# OledBoardSchematicV1.net
KiCad netlist of a schematic drawn in EAGLE
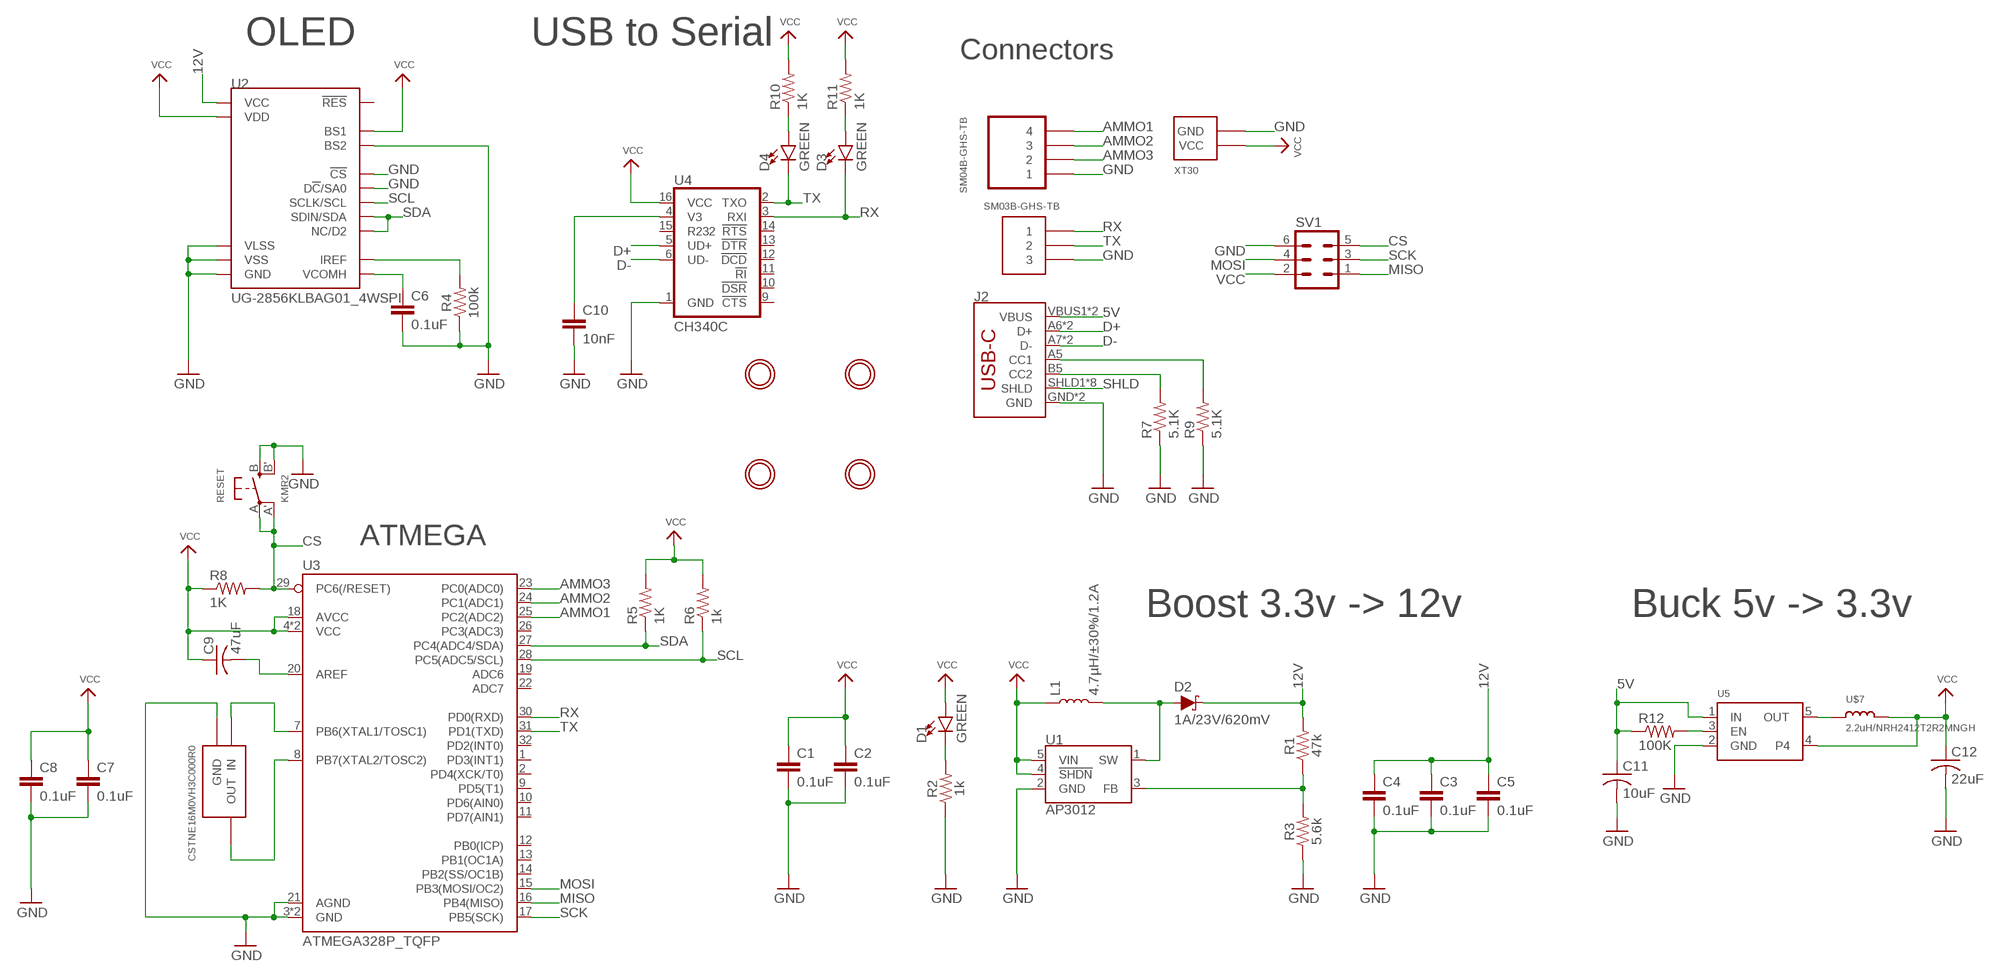
[diagram p0: schematic, sheet 1]

(export (version "E")
  (design (tool "Eeschema 10.0.6"))
  (components
    (comp (ref "C1")
      (value "0.1uF")
      (footprint "eagle-import:0603")
      (libsource (lib "eagle-import") (part "0.1UF-0603-25V-(+80/-20%)"))
    )
    (comp (ref "C2")
      (value "0.1uF")
      (footprint "eagle-import:0603")
      (libsource (lib "eagle-import") (part "0.1UF-0603-25V-(+80/-20%)"))
    )
    (comp (ref "C3")
      (value "0.1uF")
      (footprint "eagle-import:0603")
      (libsource (lib "eagle-import") (part "0.1UF-0603-25V-(+80/-20%)"))
    )
    (comp (ref "C4")
      (value "0.1uF")
      (footprint "eagle-import:0603")
      (libsource (lib "eagle-import") (part "0.1UF-0603-25V-(+80/-20%)"))
    )
    (comp (ref "C5")
      (value "0.1uF")
      (footprint "eagle-import:0603")
      (libsource (lib "eagle-import") (part "0.1UF-0603-25V-(+80/-20%)"))
    )
    (comp (ref "C6")
      (value "0.1uF")
      (footprint "eagle-import:0603")
      (libsource (lib "eagle-import") (part "0.1UF-0603-25V-(+80/-20%)"))
    )
    (comp (ref "C7")
      (value "0.1uF")
      (footprint "eagle-import:0603")
      (libsource (lib "eagle-import") (part "0.1UF-0603-25V-(+80/-20%)"))
    )
    (comp (ref "C8")
      (value "0.1uF")
      (footprint "eagle-import:0603")
      (libsource (lib "eagle-import") (part "0.1UF-0603-25V-(+80/-20%)"))
    )
    (comp (ref "C9")
      (value "47uF")
      (footprint "eagle-import:C0603")
      (libsource (lib "eagle-import") (part "C-USC0603"))
    )
    (comp (ref "C10")
      (value "10nF")
      (footprint "eagle-import:0603")
      (libsource (lib "eagle-import") (part "0.1UF-0603-25V-(+80/-20%)"))
    )
    (comp (ref "C11")
      (value "10uF")
      (footprint "eagle-import:C0603")
      (libsource (lib "eagle-import") (part "C-USC0603"))
    )
    (comp (ref "C12")
      (value "22uF")
      (footprint "eagle-import:C0603")
      (libsource (lib "eagle-import") (part "C-USC0603"))
    )
    (comp (ref "D1")
      (value "GREEN")
      (footprint "eagle-import:LED-0603")
      (libsource (lib "eagle-import") (part "LED0603"))
    )
    (comp (ref "D2")
      (value "1A/23V/620mV")
      (footprint "eagle-import:SOD-323")
      (libsource (lib "eagle-import") (part "DIODE-SCHOTTKY-BAT20J"))
    )
    (comp (ref "D3")
      (value "GREEN")
      (footprint "eagle-import:LED-0603")
      (libsource (lib "eagle-import") (part "LED-GREEN0603"))
    )
    (comp (ref "D4")
      (value "GREEN")
      (footprint "eagle-import:LED-0603")
      (libsource (lib "eagle-import") (part "LED-GREEN0603"))
    )
    (comp (ref "J2")
      (value "USB_C2-LAYER")
      (footprint "eagle-import:USB-C-16P")
      (libsource (lib "eagle-import") (part "USB_C2-LAYER"))
    )
    (comp (ref "L1")
      (value "4.7µH/±30%/1.2A")
      (footprint "eagle-import:INDUCTOR_4.7UH")
      (libsource (lib "eagle-import") (part "INDUCTOR-CDRH-4.7UH"))
    )
    (comp (ref "R1")
      (value "47k")
      (footprint "eagle-import:0603")
      (libsource (lib "eagle-import") (part "47KOHM-0603-1/10W-1%"))
    )
    (comp (ref "R2")
      (value "1k")
      (footprint "eagle-import:0603")
      (libsource (lib "eagle-import") (part "1KOHM-0603-1/10W-1%"))
    )
    (comp (ref "R3")
      (value "5.6k")
      (footprint "eagle-import:0603")
      (libsource (lib "eagle-import") (part "5.6KOHM-0603-1/10W-1%"))
    )
    (comp (ref "R4")
      (value "100k")
      (footprint "eagle-import:0603")
      (libsource (lib "eagle-import") (part "100KOHM-0603-1/10W-1%"))
    )
    (comp (ref "R5")
      (value "1K")
      (footprint "eagle-import:R0603")
      (libsource (lib "eagle-import") (part "R-US_R0603"))
    )
    (comp (ref "R6")
      (value "1k")
      (footprint "eagle-import:R0603")
      (libsource (lib "eagle-import") (part "R-US_R0603"))
    )
    (comp (ref "R7")
      (value "5.1K")
      (footprint "eagle-import:R0603")
      (libsource (lib "eagle-import") (part "R-US_R0603"))
    )
    (comp (ref "R8")
      (value "1K")
      (footprint "eagle-import:R0603")
      (libsource (lib "eagle-import") (part "R-US_R0603"))
    )
    (comp (ref "R9")
      (value "5.1K")
      (footprint "eagle-import:R0603")
      (libsource (lib "eagle-import") (part "R-US_R0603"))
    )
    (comp (ref "R10")
      (value "1K")
      (footprint "eagle-import:R0603")
      (libsource (lib "eagle-import") (part "R-US_R0603"))
    )
    (comp (ref "R11")
      (value "1K")
      (footprint "eagle-import:R0603")
      (libsource (lib "eagle-import") (part "R-US_R0603"))
    )
    (comp (ref "R12")
      (value "100K")
      (footprint "eagle-import:R0603")
      (libsource (lib "eagle-import") (part "R-US_R0603"))
    )
    (comp (ref "RESET")
      (value "KMR2")
      (footprint "eagle-import:BTN_KMR2_4.6X2.8")
      (libsource (lib "eagle-import") (part "SWITCH_TACT_SMT4.6X2.8"))
    )
    (comp (ref "SV1")
      (value "MA03-2")
      (footprint "eagle-import:MA03-2")
      (libsource (lib "eagle-import") (part "MA03-2"))
    )
    (comp (ref "U$1")
      (value "MOUNTINGHOLE2.5")
      (footprint "eagle-import:MOUNTINGHOLE_2.5_PLATED")
      (libsource (lib "eagle-import") (part "MOUNTINGHOLE2.5"))
    )
    (comp (ref "U$2")
      (value "MOUNTINGHOLE2.5")
      (footprint "eagle-import:MOUNTINGHOLE_2.5_PLATED")
      (libsource (lib "eagle-import") (part "MOUNTINGHOLE2.5"))
    )
    (comp (ref "U$3")
      (value "MOUNTINGHOLE2.5")
      (footprint "eagle-import:MOUNTINGHOLE_2.5_PLATED")
      (libsource (lib "eagle-import") (part "MOUNTINGHOLE2.5"))
    )
    (comp (ref "U$4")
      (value "MOUNTINGHOLE2.5")
      (footprint "eagle-import:MOUNTINGHOLE_2.5_PLATED")
      (libsource (lib "eagle-import") (part "MOUNTINGHOLE2.5"))
    )
    (comp (ref "U$5")
      (value "SM04B-GHS-TB")
      (footprint "eagle-import:SM04B-GHS-TB")
      (libsource (lib "eagle-import") (part "SM04B-GHS-TB"))
    )
    (comp (ref "U$6")
      (value "CSTNE16M0VH3C000R0")
      (footprint "eagle-import:CSTNE16M0VH3C000R0")
      (libsource (lib "eagle-import") (part "CSTNE16M0VH3C000R0"))
    )
    (comp (ref "U$7")
      (value "2.2uH/NRH2412T2R2MNGH")
      (footprint "eagle-import:MDKK1616T2R2MM")
      (libsource (lib "eagle-import") (part "MDKK1616T2R2MM"))
    )
    (comp (ref "U$8")
      (value "SM03B-GHS-TB")
      (footprint "eagle-import:SM03B-GHS-TB")
      (libsource (lib "eagle-import") (part "SM03B-GHS-TB"))
    )
    (comp (ref "U$9")
      (value "XT30PW-M")
      (footprint "eagle-import:XT30")
      (libsource (lib "eagle-import") (part "XT30PW-M"))
    )
    (comp (ref "U1")
      (value "AP3012")
      (footprint "eagle-import:SOT23-5")
      (libsource (lib "eagle-import") (part "AP3012"))
    )
    (comp (ref "U2")
      (value "UG-2856KLBAG01_4WSPI")
      (footprint "eagle-import:FPC05024-42201")
      (libsource (lib "eagle-import") (part "UG-2856KLBAG01_4WSPI"))
    )
    (comp (ref "U3")
      (value "ATMEGA328P_TQFP")
      (footprint "eagle-import:TQFP32-08")
      (libsource (lib "eagle-import") (part "ATMEGA328P_TQFP"))
    )
    (comp (ref "U4")
      (value "CH340C")
      (footprint "eagle-import:SO016")
      (libsource (lib "eagle-import") (part "CH340C"))
    )
    (comp (ref "U5")
      (value "VREG_SOT23-5")
      (footprint "eagle-import:SOT23-5")
      (libsource (lib "eagle-import") (part "VREG_SOT23-5"))
    )
  )
  (nets
    (net (code "1") (name "/5V") (class "Default")
      (node (ref "C11") (pin "1") (pinfunction "1_1") (pintype "passive"))
      (node (ref "J2") (pin "VBUS1") (pinfunction "VBUS_VBUS1") (pintype "bidirectional"))
      (node (ref "J2") (pin "VBUS2") (pinfunction "VBUS_VBUS2") (pintype "bidirectional"))
      (node (ref "R12") (pin "1") (pinfunction "1_1") (pintype "passive"))
      (node (ref "U5") (pin "1") (pinfunction "IN_1") (pintype "bidirectional"))
    )
    (net (code "2") (name "/12V") (class "Default")
      (node (ref "C3") (pin "1") (pinfunction "1_1") (pintype "passive"))
      (node (ref "C4") (pin "1") (pinfunction "1_1") (pintype "passive"))
      (node (ref "C5") (pin "1") (pinfunction "1_1") (pintype "passive"))
      (node (ref "D2") (pin "C") (pinfunction "C_C") (pintype "passive"))
      (node (ref "R1") (pin "2") (pinfunction "2_2") (pintype "passive"))
      (node (ref "U2") (pin "P$23") (pinfunction "VCC_P$23") (pintype "bidirectional"))
    )
    (net (code "3") (name "/AMMO1") (class "Default")
      (node (ref "U$5") (pin "4") (pinfunction "4_4") (pintype "bidirectional"))
      (node (ref "U3") (pin "25") (pinfunction "PC2(ADC2)_25") (pintype "bidirectional"))
    )
    (net (code "4") (name "/AMMO2") (class "Default")
      (node (ref "U$5") (pin "3") (pinfunction "3_3") (pintype "bidirectional"))
      (node (ref "U3") (pin "24") (pinfunction "PC1(ADC1)_24") (pintype "bidirectional"))
    )
    (net (code "5") (name "/AMMO3") (class "Default")
      (node (ref "U$5") (pin "2") (pinfunction "2_2") (pintype "bidirectional"))
      (node (ref "U3") (pin "23") (pinfunction "PC0(ADC0)_23") (pintype "bidirectional"))
    )
    (net (code "6") (name "/CS") (class "Default")
      (node (ref "R8") (pin "2") (pinfunction "2_2") (pintype "passive"))
      (node (ref "RESET") (pin "A") (pinfunction "P_A") (pintype "passive"))
      (node (ref "RESET") (pin "A'") (pinfunction "P1_A'") (pintype "passive"))
      (node (ref "SV1") (pin "5") (pinfunction "5_5") (pintype "passive"))
      (node (ref "U3") (pin "29") (pinfunction "PC6(/RESET)_29") (pintype "bidirectional"))
    )
    (net (code "7") (name "/D+") (class "Default")
      (node (ref "J2") (pin "A6") (pinfunction "D+_A6") (pintype "bidirectional"))
      (node (ref "J2") (pin "B6") (pinfunction "D+_B6") (pintype "bidirectional"))
      (node (ref "U4") (pin "5") (pinfunction "UD+_5") (pintype "bidirectional"))
    )
    (net (code "8") (name "/D-") (class "Default")
      (node (ref "J2") (pin "A7") (pinfunction "D-_A7") (pintype "bidirectional"))
      (node (ref "J2") (pin "B7") (pinfunction "D-_B7") (pintype "bidirectional"))
      (node (ref "U4") (pin "6") (pinfunction "UD-_6") (pintype "bidirectional"))
    )
    (net (code "9") (name "/MISO") (class "Default")
      (node (ref "SV1") (pin "1") (pinfunction "1_1") (pintype "passive"))
      (node (ref "U3") (pin "16") (pinfunction "PB4(MISO)_16") (pintype "bidirectional"))
    )
    (net (code "10") (name "/MOSI") (class "Default")
      (node (ref "SV1") (pin "4") (pinfunction "4_4") (pintype "passive"))
      (node (ref "U3") (pin "15") (pinfunction "PB3(MOSI/OC2)_15") (pintype "bidirectional"))
    )
    (net (code "11") (name "/RX") (class "Default")
      (node (ref "D3") (pin "C") (pinfunction "C_C") (pintype "passive"))
      (node (ref "U$8") (pin "P$3") (pinfunction "1_P$3") (pintype "bidirectional"))
      (node (ref "U3") (pin "30") (pinfunction "PD0(RXD)_30") (pintype "bidirectional"))
      (node (ref "U4") (pin "3") (pinfunction "RXI_3") (pintype "bidirectional"))
    )
    (net (code "12") (name "/SCK") (class "Default")
      (node (ref "SV1") (pin "3") (pinfunction "3_3") (pintype "passive"))
      (node (ref "U3") (pin "17") (pinfunction "PB5(SCK)_17") (pintype "bidirectional"))
    )
    (net (code "13") (name "/SCL") (class "Default")
      (node (ref "R6") (pin "1") (pinfunction "1_1") (pintype "passive"))
      (node (ref "U2") (pin "P$13") (pinfunction "SCLK/SCL_P$13") (pintype "bidirectional"))
      (node (ref "U3") (pin "28") (pinfunction "PC5(ADC5/SCL)_28") (pintype "bidirectional"))
    )
    (net (code "14") (name "/SDA") (class "Default")
      (node (ref "R5") (pin "1") (pinfunction "1_1") (pintype "passive"))
      (node (ref "U2") (pin "P$14") (pinfunction "SDIN/SDA_P$14") (pintype "bidirectional"))
      (node (ref "U2") (pin "P$15") (pinfunction "NC/D2_P$15") (pintype "bidirectional"))
      (node (ref "U3") (pin "27") (pinfunction "PC4(ADC4/SDA)_27") (pintype "bidirectional"))
    )
    (net (code "15") (name "/SHLD") (class "Default")
      (node (ref "J2") (pin "SHLD1") (pinfunction "SHLD_SHLD1") (pintype "bidirectional"))
      (node (ref "J2") (pin "SHLD2") (pinfunction "SHLD_SHLD2") (pintype "bidirectional"))
      (node (ref "J2") (pin "SHLD3") (pinfunction "SHLD_SHLD3") (pintype "bidirectional"))
      (node (ref "J2") (pin "SHLD4") (pinfunction "SHLD_SHLD4") (pintype "bidirectional"))
      (node (ref "J2") (pin "SHLD5") (pinfunction "SHLD_SHLD5") (pintype "bidirectional"))
      (node (ref "J2") (pin "SHLD6") (pinfunction "SHLD_SHLD6") (pintype "bidirectional"))
      (node (ref "J2") (pin "SHLD7") (pinfunction "SHLD_SHLD7") (pintype "bidirectional"))
      (node (ref "J2") (pin "SHLD8") (pinfunction "SHLD_SHLD8") (pintype "bidirectional"))
    )
    (net (code "16") (name "/TX") (class "Default")
      (node (ref "D4") (pin "C") (pinfunction "C_C") (pintype "passive"))
      (node (ref "U$8") (pin "P$4") (pinfunction "2_P$4") (pintype "bidirectional"))
      (node (ref "U3") (pin "31") (pinfunction "PD1(TXD)_31") (pintype "bidirectional"))
      (node (ref "U4") (pin "2") (pinfunction "TXO_2") (pintype "bidirectional"))
    )
    (net (code "17") (name "GND") (class "Default")
      (node (ref "C1") (pin "2") (pinfunction "2_2") (pintype "passive"))
      (node (ref "C10") (pin "2") (pinfunction "2_2") (pintype "passive"))
      (node (ref "C11") (pin "2") (pinfunction "2_2") (pintype "passive"))
      (node (ref "C12") (pin "2") (pinfunction "2_2") (pintype "passive"))
      (node (ref "C2") (pin "2") (pinfunction "2_2") (pintype "passive"))
      (node (ref "C3") (pin "2") (pinfunction "2_2") (pintype "passive"))
      (node (ref "C4") (pin "2") (pinfunction "2_2") (pintype "passive"))
      (node (ref "C5") (pin "2") (pinfunction "2_2") (pintype "passive"))
      (node (ref "C6") (pin "2") (pinfunction "2_2") (pintype "passive"))
      (node (ref "C7") (pin "2") (pinfunction "2_2") (pintype "passive"))
      (node (ref "C8") (pin "2") (pinfunction "2_2") (pintype "passive"))
      (node (ref "J2") (pin "GND") (pinfunction "GND_GND") (pintype "bidirectional"))
      (node (ref "J2") (pin "GND2") (pinfunction "GND_GND2") (pintype "bidirectional"))
      (node (ref "R2") (pin "1") (pinfunction "1_1") (pintype "passive"))
      (node (ref "R3") (pin "1") (pinfunction "1_1") (pintype "passive"))
      (node (ref "R4") (pin "1") (pinfunction "1_1") (pintype "passive"))
      (node (ref "R7") (pin "1") (pinfunction "1_1") (pintype "passive"))
      (node (ref "R9") (pin "1") (pinfunction "1_1") (pintype "passive"))
      (node (ref "RESET") (pin "B") (pinfunction "S_B") (pintype "passive"))
      (node (ref "RESET") (pin "B'") (pinfunction "S1_B'") (pintype "passive"))
      (node (ref "SV1") (pin "6") (pinfunction "6_6") (pintype "passive"))
      (node (ref "U$5") (pin "1") (pinfunction "1_1") (pintype "bidirectional"))
      (node (ref "U$6") (pin "2") (pinfunction "GND_2") (pintype "bidirectional"))
      (node (ref "U$8") (pin "P$5") (pinfunction "3_P$5") (pintype "bidirectional"))
      (node (ref "U$9") (pin "P$2") (pinfunction "GND_P$2") (pintype "bidirectional"))
      (node (ref "U1") (pin "2") (pinfunction "GND_2") (pintype "bidirectional"))
      (node (ref "U2") (pin "P$1") (pinfunction "GND_P$1") (pintype "bidirectional"))
      (node (ref "U2") (pin "P$10") (pinfunction "D~{C}/SA0_P$10") (pintype "bidirectional"))
      (node (ref "U2") (pin "P$11") (pinfunction "GND_P$11") (pintype "bidirectional"))
      (node (ref "U2") (pin "P$12") (pinfunction "GND_P$12") (pintype "bidirectional"))
      (node (ref "U2") (pin "P$16") (pinfunction "GND_P$16") (pintype "bidirectional"))
      (node (ref "U2") (pin "P$17") (pinfunction "GND_P$17") (pintype "bidirectional"))
      (node (ref "U2") (pin "P$18") (pinfunction "GND_P$18") (pintype "bidirectional"))
      (node (ref "U2") (pin "P$19") (pinfunction "GND_P$19") (pintype "bidirectional"))
      (node (ref "U2") (pin "P$2") (pinfunction "VLSS_P$2") (pintype "bidirectional"))
      (node (ref "U2") (pin "P$20") (pinfunction "GND_P$20") (pintype "bidirectional"))
      (node (ref "U2") (pin "P$24") (pinfunction "GND_P$24") (pintype "bidirectional"))
      (node (ref "U2") (pin "P$3") (pinfunction "VSS_P$3") (pintype "bidirectional"))
      (node (ref "U2") (pin "P$7") (pinfunction "BS2_P$7") (pintype "bidirectional"))
      (node (ref "U2") (pin "P$8") (pinfunction "~{CS}_P$8") (pintype "bidirectional"))
      (node (ref "U3") (pin "21") (pinfunction "AGND_21") (pintype "bidirectional"))
      (node (ref "U3") (pin "3") (pinfunction "GND_3") (pintype "bidirectional"))
      (node (ref "U3") (pin "5") (pinfunction "GND_5") (pintype "bidirectional"))
      (node (ref "U4") (pin "1") (pinfunction "GND_1") (pintype "bidirectional"))
      (node (ref "U5") (pin "2") (pinfunction "GND_2") (pintype "bidirectional"))
    )
    (net (code "18") (name "Net-(D1-PadC)") (class "Default")
      (node (ref "D1") (pin "C") (pinfunction "C_C") (pintype "passive"))
      (node (ref "R2") (pin "2") (pinfunction "2_2") (pintype "passive"))
    )
    (net (code "19") (name "Net-(D3-PadA)") (class "Default")
      (node (ref "D3") (pin "A") (pinfunction "A_A") (pintype "passive"))
      (node (ref "R11") (pin "1") (pinfunction "1_1") (pintype "passive"))
    )
    (net (code "20") (name "Net-(D4-PadA)") (class "Default")
      (node (ref "D4") (pin "A") (pinfunction "A_A") (pintype "passive"))
      (node (ref "R10") (pin "1") (pinfunction "1_1") (pintype "passive"))
    )
    (net (code "21") (name "Net-(J2-CC1)") (class "Default")
      (node (ref "J2") (pin "A5") (pinfunction "CC1_A5") (pintype "bidirectional"))
      (node (ref "R9") (pin "2") (pinfunction "2_2") (pintype "passive"))
    )
    (net (code "22") (name "Net-(J2-CC2)") (class "Default")
      (node (ref "J2") (pin "B5") (pinfunction "CC2_B5") (pintype "bidirectional"))
      (node (ref "R7") (pin "2") (pinfunction "2_2") (pintype "passive"))
    )
    (net (code "23") (name "Net-(L1-2)") (class "Default")
      (node (ref "D2") (pin "A") (pinfunction "A_A") (pintype "passive"))
      (node (ref "L1") (pin "P$2") (pinfunction "2_P$2") (pintype "passive"))
      (node (ref "U1") (pin "1") (pinfunction "SW_1") (pintype "bidirectional"))
    )
    (net (code "24") (name "Net-(U$6-IN)") (class "Default")
      (node (ref "U$6") (pin "1") (pinfunction "IN_1") (pintype "bidirectional"))
      (node (ref "U3") (pin "7") (pinfunction "PB6(XTAL1/TOSC1)_7") (pintype "bidirectional"))
    )
    (net (code "25") (name "Net-(U$6-OUT)") (class "Default")
      (node (ref "U$6") (pin "3") (pinfunction "OUT_3") (pintype "bidirectional"))
      (node (ref "U3") (pin "8") (pinfunction "PB7(XTAL2/TOSC2)_8") (pintype "bidirectional"))
    )
    (net (code "26") (name "Net-(U$7-1)") (class "Default")
      (node (ref "U$7") (pin "P$1") (pinfunction "1_P$1") (pintype "passive"))
      (node (ref "U5") (pin "5") (pinfunction "OUT_5") (pintype "bidirectional"))
    )
    (net (code "27") (name "Net-(U1-FB)") (class "Default")
      (node (ref "R1") (pin "1") (pinfunction "1_1") (pintype "passive"))
      (node (ref "R3") (pin "2") (pinfunction "2_2") (pintype "passive"))
      (node (ref "U1") (pin "3") (pinfunction "FB_3") (pintype "bidirectional"))
    )
    (net (code "28") (name "Net-(U2-IREF)") (class "Default")
      (node (ref "R4") (pin "2") (pinfunction "2_2") (pintype "passive"))
      (node (ref "U2") (pin "P$21") (pinfunction "IREF_P$21") (pintype "bidirectional"))
    )
    (net (code "29") (name "Net-(U2-VCOMH)") (class "Default")
      (node (ref "C6") (pin "1") (pinfunction "1_1") (pintype "passive"))
      (node (ref "U2") (pin "P$22") (pinfunction "VCOMH_P$22") (pintype "bidirectional"))
    )
    (net (code "30") (name "Net-(U3-AREF)") (class "Default")
      (node (ref "C9") (pin "2") (pinfunction "2_2") (pintype "passive"))
      (node (ref "U3") (pin "20") (pinfunction "AREF_20") (pintype "bidirectional"))
    )
    (net (code "31") (name "Net-(U4-V3)") (class "Default")
      (node (ref "C10") (pin "1") (pinfunction "1_1") (pintype "passive"))
      (node (ref "U4") (pin "4") (pinfunction "V3_4") (pintype "bidirectional"))
    )
    (net (code "32") (name "Net-(U5-EN)") (class "Default")
      (node (ref "R12") (pin "2") (pinfunction "2_2") (pintype "passive"))
      (node (ref "U5") (pin "3") (pinfunction "EN_3") (pintype "bidirectional"))
    )
    (net (code "33") (name "VCC") (class "Default")
      (node (ref "C1") (pin "1") (pinfunction "1_1") (pintype "passive"))
      (node (ref "C12") (pin "1") (pinfunction "1_1") (pintype "passive"))
      (node (ref "C2") (pin "1") (pinfunction "1_1") (pintype "passive"))
      (node (ref "C7") (pin "1") (pinfunction "1_1") (pintype "passive"))
      (node (ref "C8") (pin "1") (pinfunction "1_1") (pintype "passive"))
      (node (ref "C9") (pin "1") (pinfunction "1_1") (pintype "passive"))
      (node (ref "D1") (pin "A") (pinfunction "A_A") (pintype "passive"))
      (node (ref "L1") (pin "P$1") (pinfunction "1_P$1") (pintype "passive"))
      (node (ref "R10") (pin "2") (pinfunction "2_2") (pintype "passive"))
      (node (ref "R11") (pin "2") (pinfunction "2_2") (pintype "passive"))
      (node (ref "R5") (pin "2") (pinfunction "2_2") (pintype "passive"))
      (node (ref "R6") (pin "2") (pinfunction "2_2") (pintype "passive"))
      (node (ref "R8") (pin "1") (pinfunction "1_1") (pintype "passive"))
      (node (ref "SV1") (pin "2") (pinfunction "2_2") (pintype "passive"))
      (node (ref "U$7") (pin "P$2") (pinfunction "2_P$2") (pintype "passive"))
      (node (ref "U$9") (pin "P$1") (pinfunction "VCC_P$1") (pintype "bidirectional"))
      (node (ref "U1") (pin "4") (pinfunction "~{SHDN}_4") (pintype "bidirectional"))
      (node (ref "U1") (pin "5") (pinfunction "VIN_5") (pintype "bidirectional"))
      (node (ref "U2") (pin "P$5") (pinfunction "VDD_P$5") (pintype "bidirectional"))
      (node (ref "U2") (pin "P$6") (pinfunction "BS1_P$6") (pintype "bidirectional"))
      (node (ref "U3") (pin "18") (pinfunction "AVCC_18") (pintype "bidirectional"))
      (node (ref "U3") (pin "4") (pinfunction "VCC_4") (pintype "bidirectional"))
      (node (ref "U3") (pin "6") (pinfunction "VCC_6") (pintype "bidirectional"))
      (node (ref "U4") (pin "16") (pinfunction "VCC_16") (pintype "bidirectional"))
      (node (ref "U5") (pin "4") (pinfunction "P4_4") (pintype "bidirectional"))
    )
    (net (code "34") (name "unconnected-(U2-~{RES}-PadP$9)") (class "Default")
      (node (ref "U2") (pin "P$9") (pinfunction "~{RES}_P$9") (pintype "bidirectional"))
    )
    (net (code "35") (name "unconnected-(U3-ADC6-Pad19)") (class "Default")
      (node (ref "U3") (pin "19") (pinfunction "ADC6_19") (pintype "bidirectional"))
    )
    (net (code "36") (name "unconnected-(U3-ADC7-Pad22)") (class "Default")
      (node (ref "U3") (pin "22") (pinfunction "ADC7_22") (pintype "bidirectional"))
    )
    (net (code "37") (name "unconnected-(U3-PB0(ICP)-Pad12)") (class "Default")
      (node (ref "U3") (pin "12") (pinfunction "PB0(ICP)_12") (pintype "bidirectional"))
    )
    (net (code "38") (name "unconnected-(U3-PB1(OC1A)-Pad13)") (class "Default")
      (node (ref "U3") (pin "13") (pinfunction "PB1(OC1A)_13") (pintype "bidirectional"))
    )
    (net (code "39") (name "unconnected-(U3-PB2(SS{slash}OC1B)-Pad14)") (class "Default")
      (node (ref "U3") (pin "14") (pinfunction "PB2(SS/OC1B)_14") (pintype "bidirectional"))
    )
    (net (code "40") (name "unconnected-(U3-PC3(ADC3)-Pad26)") (class "Default")
      (node (ref "U3") (pin "26") (pinfunction "PC3(ADC3)_26") (pintype "bidirectional"))
    )
    (net (code "41") (name "unconnected-(U3-PD2(INT0)-Pad32)") (class "Default")
      (node (ref "U3") (pin "32") (pinfunction "PD2(INT0)_32") (pintype "bidirectional"))
    )
    (net (code "42") (name "unconnected-(U3-PD3(INT1)-Pad1)") (class "Default")
      (node (ref "U3") (pin "1") (pinfunction "PD3(INT1)_1") (pintype "bidirectional"))
    )
    (net (code "43") (name "unconnected-(U3-PD4(XCK{slash}T0)-Pad2)") (class "Default")
      (node (ref "U3") (pin "2") (pinfunction "PD4(XCK/T0)_2") (pintype "bidirectional"))
    )
    (net (code "44") (name "unconnected-(U3-PD5(T1)-Pad9)") (class "Default")
      (node (ref "U3") (pin "9") (pinfunction "PD5(T1)_9") (pintype "bidirectional"))
    )
    (net (code "45") (name "unconnected-(U3-PD6(AIN0)-Pad10)") (class "Default")
      (node (ref "U3") (pin "10") (pinfunction "PD6(AIN0)_10") (pintype "bidirectional"))
    )
    (net (code "46") (name "unconnected-(U3-PD7(AIN1)-Pad11)") (class "Default")
      (node (ref "U3") (pin "11") (pinfunction "PD7(AIN1)_11") (pintype "bidirectional"))
    )
    (net (code "47") (name "unconnected-(U4-R232-Pad15)") (class "Default")
      (node (ref "U4") (pin "15") (pinfunction "R232_15") (pintype "bidirectional"))
    )
    (net (code "48") (name "unconnected-(U4-~{CTS}-Pad9)") (class "Default")
      (node (ref "U4") (pin "9") (pinfunction "~{CTS}_9") (pintype "bidirectional"))
    )
    (net (code "49") (name "unconnected-(U4-~{DCD}-Pad12)") (class "Default")
      (node (ref "U4") (pin "12") (pinfunction "~{DCD}_12") (pintype "bidirectional"))
    )
    (net (code "50") (name "unconnected-(U4-~{DSR}-Pad10)") (class "Default")
      (node (ref "U4") (pin "10") (pinfunction "~{DSR}_10") (pintype "bidirectional"))
    )
    (net (code "51") (name "unconnected-(U4-~{DTR}-Pad13)") (class "Default")
      (node (ref "U4") (pin "13") (pinfunction "~{DTR}_13") (pintype "bidirectional"))
    )
    (net (code "52") (name "unconnected-(U4-~{RI}-Pad11)") (class "Default")
      (node (ref "U4") (pin "11") (pinfunction "~{RI}_11") (pintype "bidirectional"))
    )
    (net (code "53") (name "unconnected-(U4-~{RTS}-Pad14)") (class "Default")
      (node (ref "U4") (pin "14") (pinfunction "~{RTS}_14") (pintype "bidirectional"))
    )
  )
)
